# mazeSolver.net
KiCad netlist of a schematic drawn in EAGLE
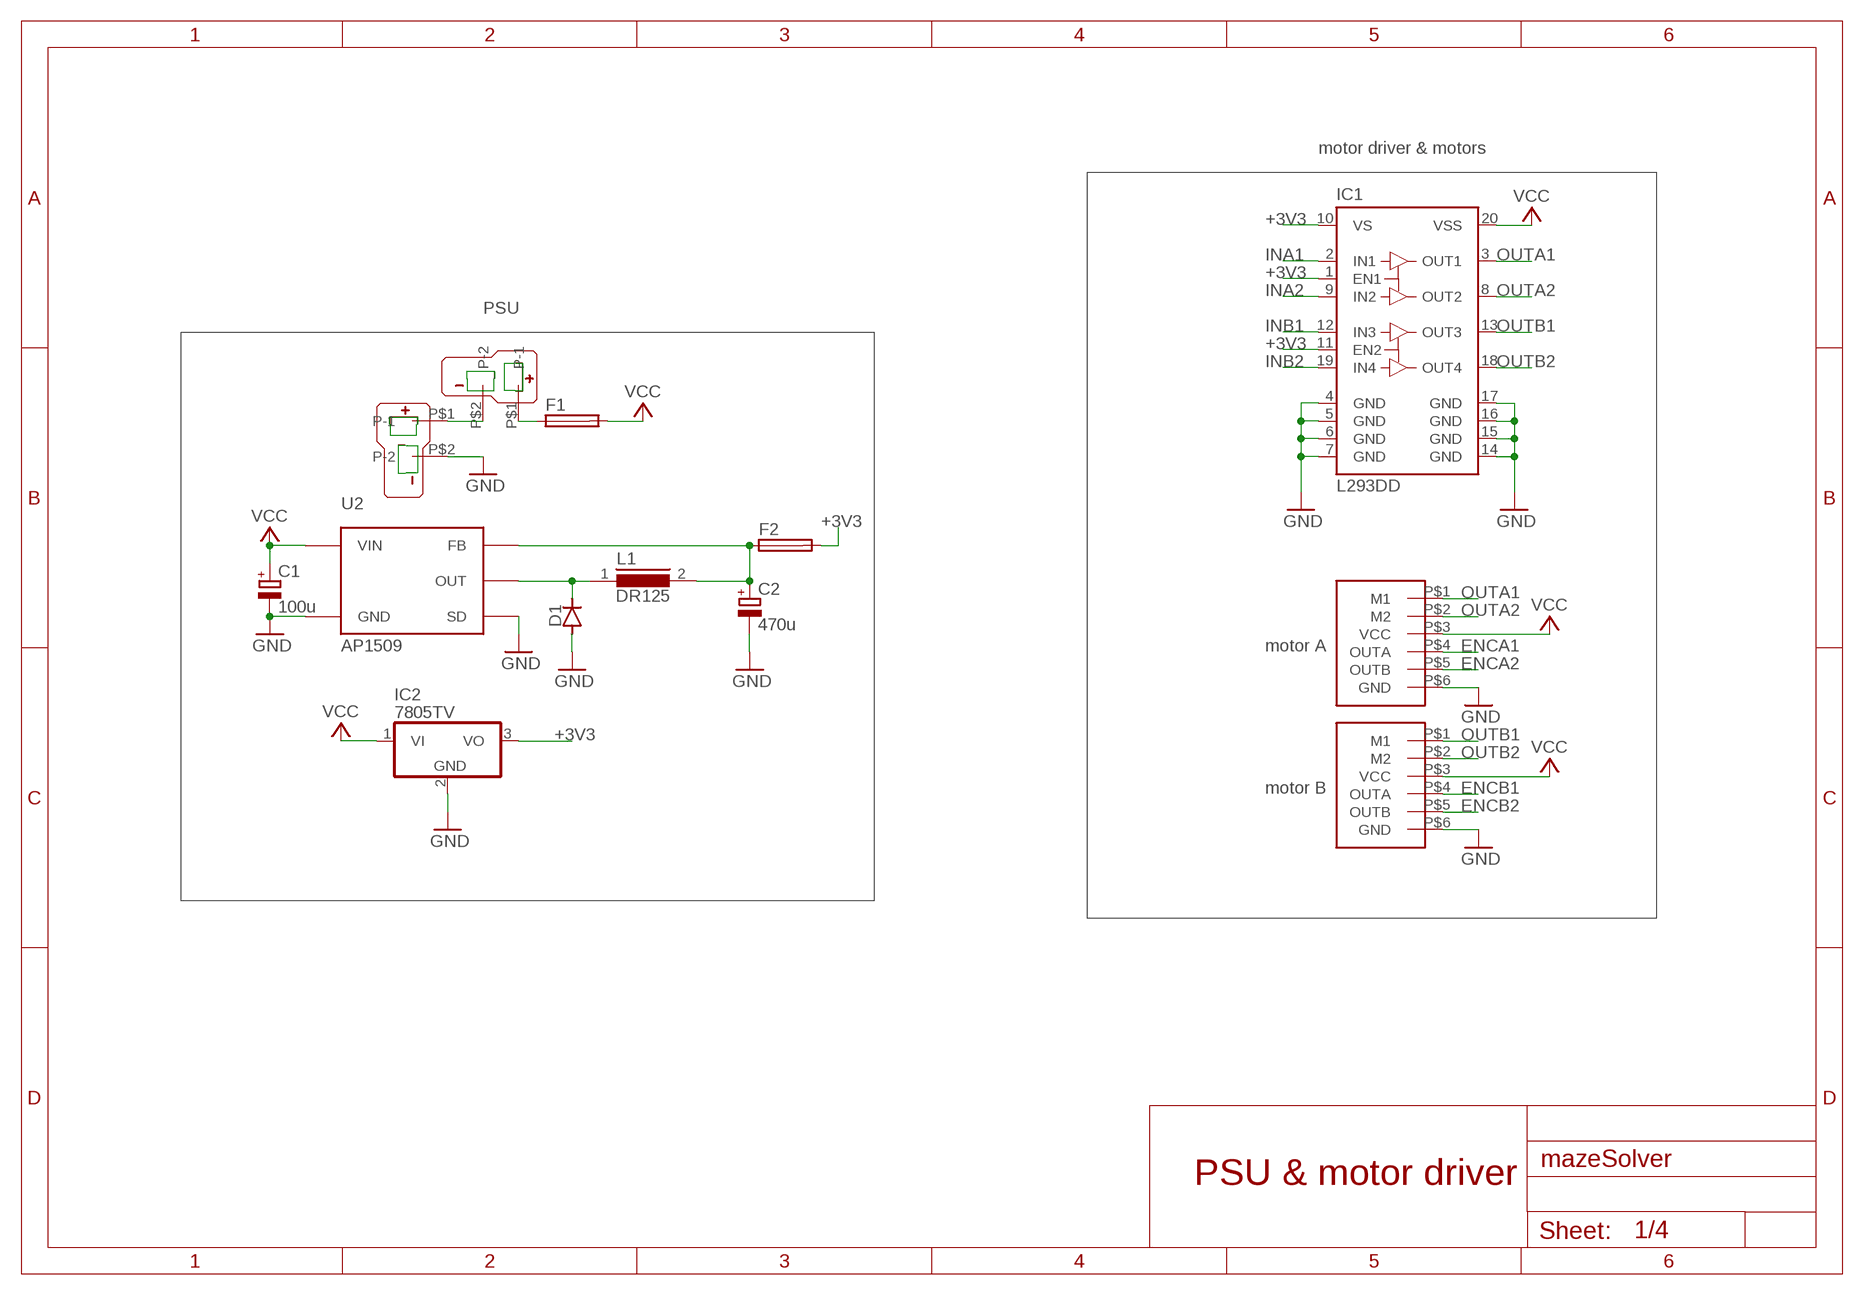
[diagram p0: schematic, sheet 1]
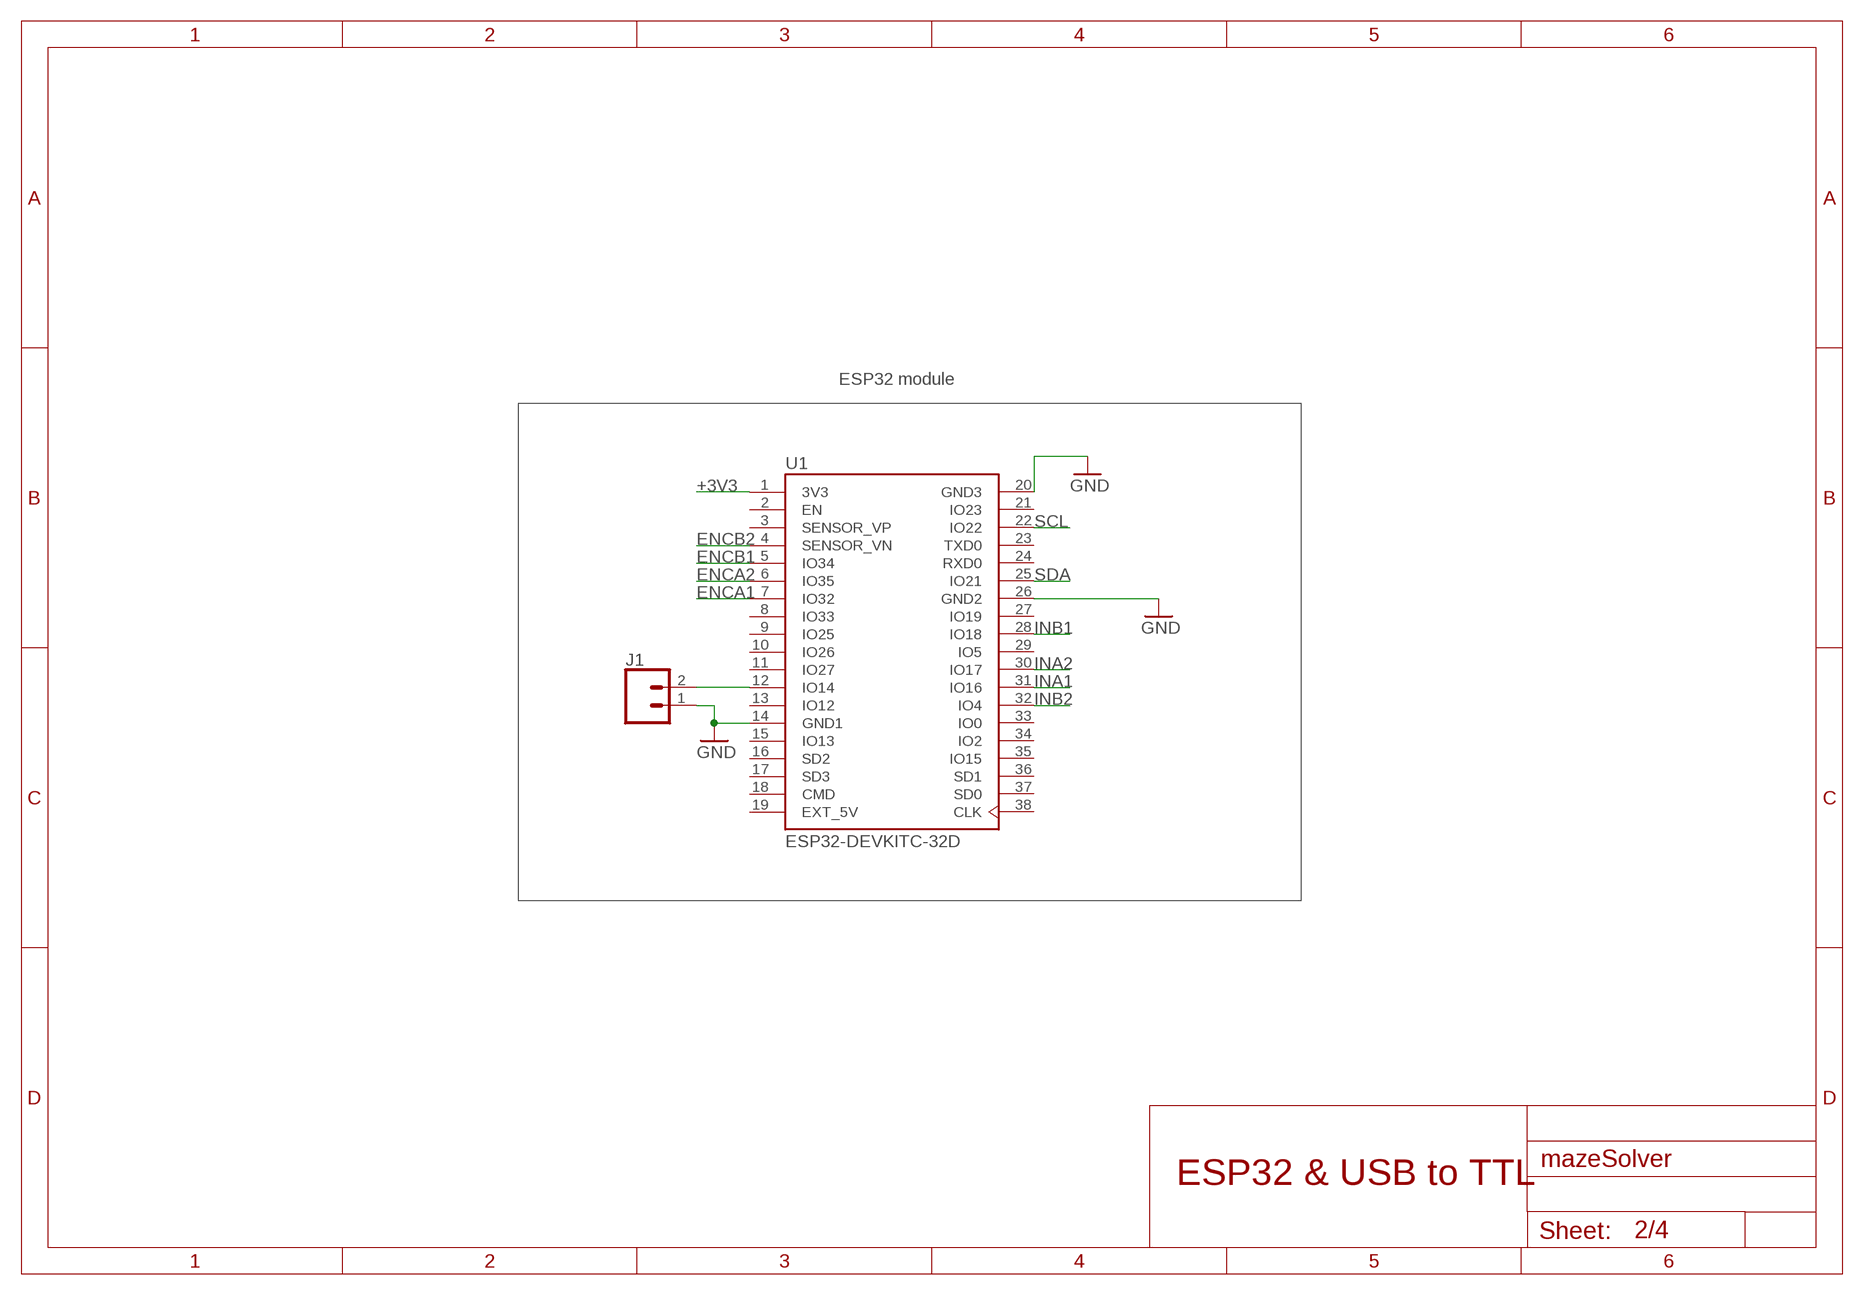
[diagram p1: schematic, sheet 2]
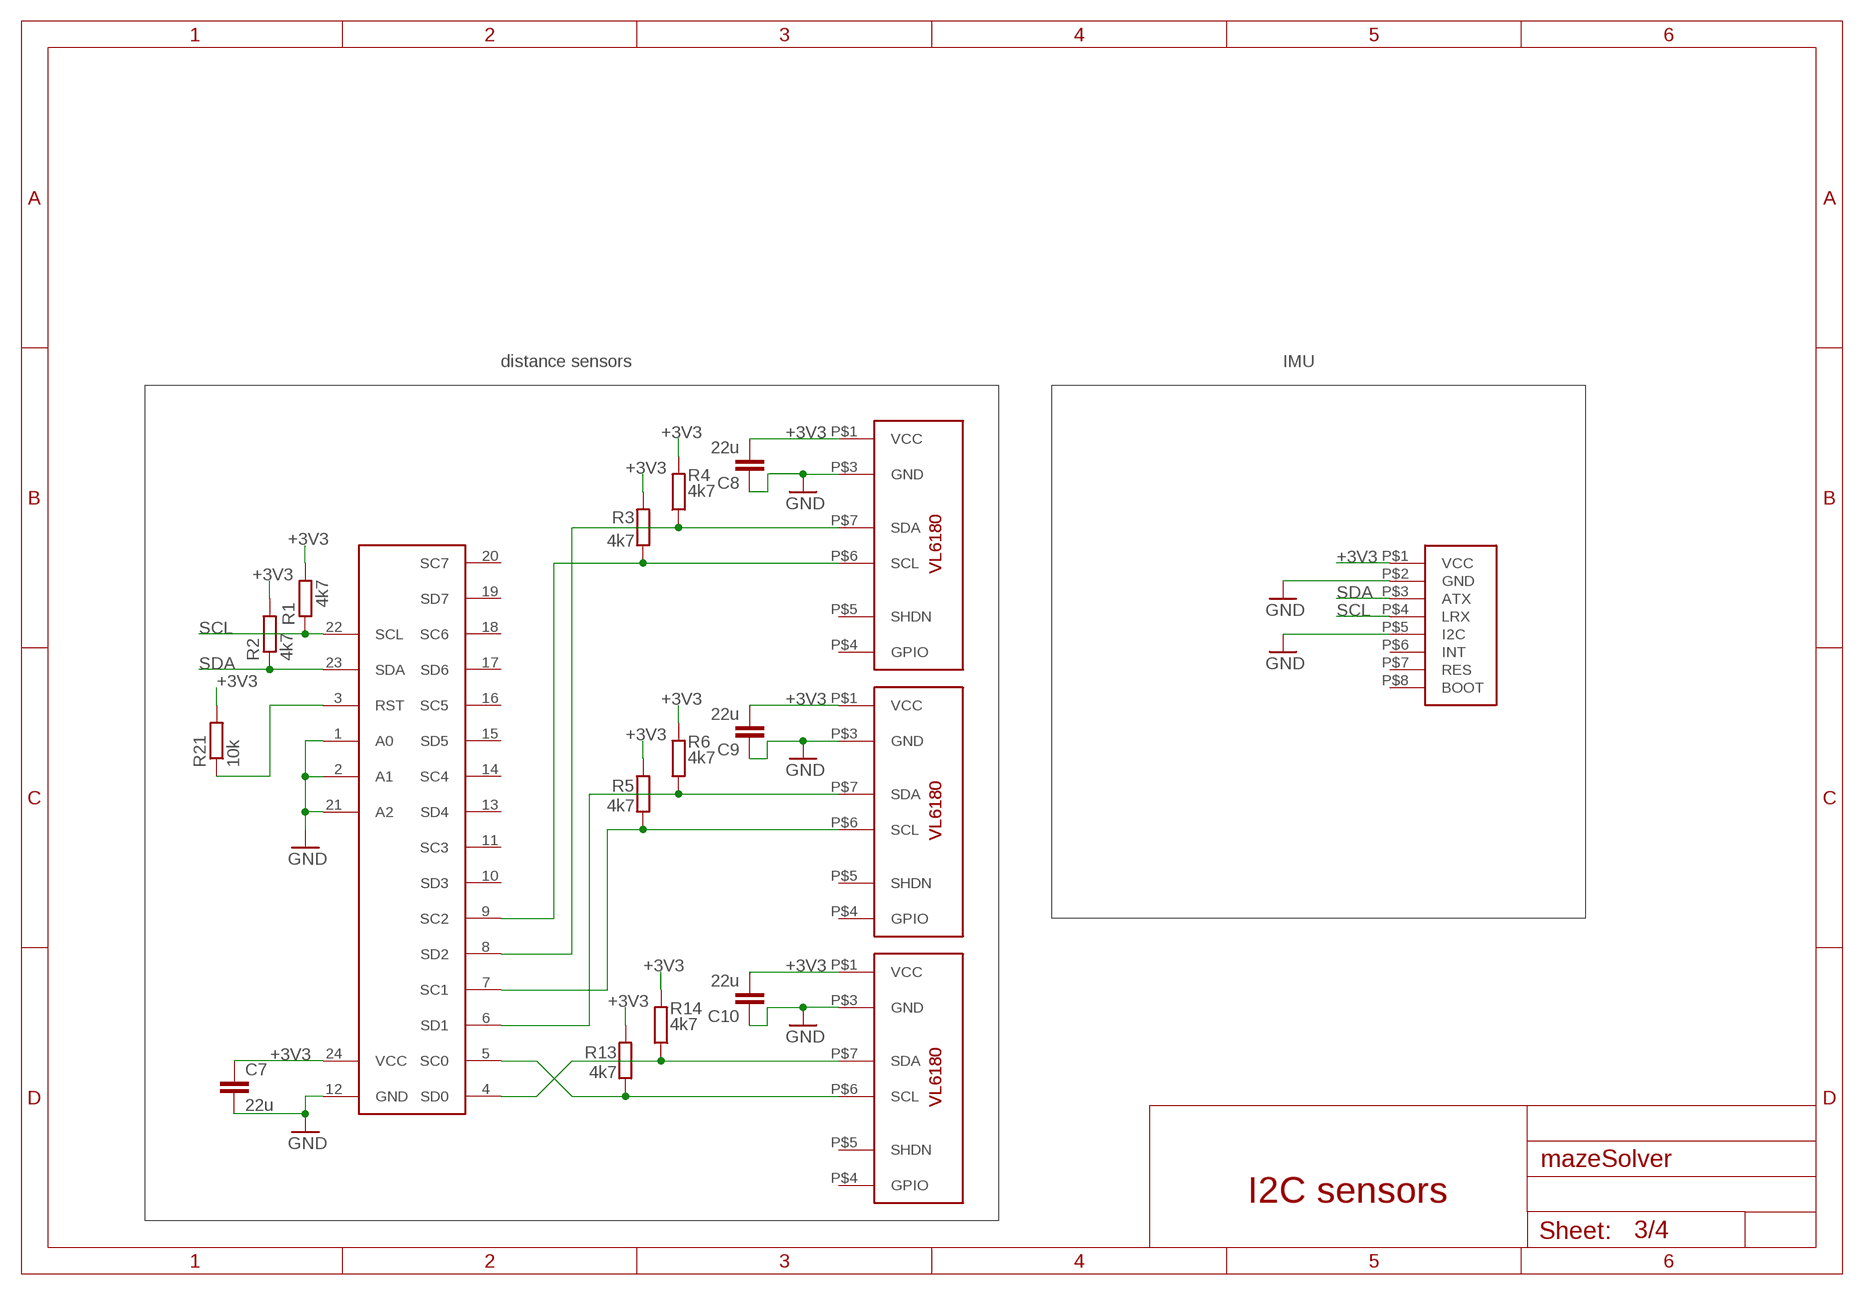
[diagram p2: schematic, sheet 3]

(export (version "E")
  (design (tool "Eeschema 10.0.6"))
  (components
    (comp (ref "J1")
      (value "CONN_02")
      (footprint "eagle-import:1X02")
      (libsource (lib "eagle-import") (part "CONN_02"))
    )
    (comp (ref "U1")
      (value "ESP32-DEVKITC-32D")
      (footprint "eagle-import:MODULE_ESP32-DEVKITC-32D")
      (fields (field (name "MF") "Espressif Systems"))
      (libsource (lib "eagle-import") (part "ESP32-DEVKITC-32D"))
    )
    (comp (ref "C1")
      (value "100u")
      (footprint "eagle-import:140CLH-0810")
      (fields (field (name "MF") "RUBYCON") (field (name "MPN") "100YXF100MEFC12.5X20"))
      (libsource (lib "eagle-import") (part "CPOL-EU140CLH-0810"))
    )
    (comp (ref "C2")
      (value "470u")
      (footprint "eagle-import:140CLH-0810")
      (libsource (lib "eagle-import") (part "CPOL-EU140CLH-0810"))
    )
    (comp (ref "D1")
      (value "DIODE-DO214AC")
      (footprint "eagle-import:DO214AC")
      (libsource (lib "eagle-import") (part "DIODE-DO214AC"))
    )
    (comp (ref "F1")
      (value "195591812")
      (footprint "eagle-import:C1812K")
      (libsource (lib "eagle-import") (part "195591812"))
    )
    (comp (ref "F2")
      (value "195591206")
      (footprint "eagle-import:C1206K")
      (libsource (lib "eagle-import") (part "195591206"))
    )
    (comp (ref "IC1")
      (value "L293DD")
      (footprint "eagle-import:SO20")
      (libsource (lib "eagle-import") (part "L293DD"))
    )
    (comp (ref "IC2")
      (value "7805TV")
      (footprint "eagle-import:TO220V")
      (libsource (lib "eagle-import") (part "78TV05"))
    )
    (comp (ref "L1")
      (value "DR125")
      (footprint "eagle-import:DR125")
      (libsource (lib "eagle-import") (part "DR125"))
    )
    (comp (ref "U$1")
      (value "T-PLUG_CONNECTOR")
      (footprint "eagle-import:T_PLUG_CONNECTOR")
      (libsource (lib "eagle-import") (part "T-PLUG_CONNECTOR"))
    )
    (comp (ref "U$2")
      (value "POLOLU_ENCODER")
      (footprint "eagle-import:POLOLU_ENCODER")
      (libsource (lib "eagle-import") (part "POLOLU_ENCODER"))
    )
    (comp (ref "U$3")
      (value "POLOLU_ENCODER")
      (footprint "eagle-import:POLOLU_ENCODER")
      (libsource (lib "eagle-import") (part "POLOLU_ENCODER"))
    )
    (comp (ref "U$9")
      (value "T-PLUG_CONNECTOR")
      (footprint "eagle-import:T_PLUG_CONNECTOR")
      (libsource (lib "eagle-import") (part "T-PLUG_CONNECTOR"))
    )
    (comp (ref "U2")
      (value "AP1509-SOP8L")
      (footprint "eagle-import:SOP-8L")
      (libsource (lib "eagle-import") (part "AP1509-SOP8L"))
    )
    (comp (ref "C7")
      (value "22u")
      (footprint "eagle-import:C1206")
      (libsource (lib "eagle-import") (part "C-EUC1206"))
    )
    (comp (ref "C8")
      (value "22u")
      (footprint "eagle-import:C1206")
      (libsource (lib "eagle-import") (part "C-EUC1206"))
    )
    (comp (ref "C9")
      (value "22u")
      (footprint "eagle-import:C1206")
      (libsource (lib "eagle-import") (part "C-EUC1206"))
    )
    (comp (ref "C10")
      (value "22u")
      (footprint "eagle-import:C1206")
      (libsource (lib "eagle-import") (part "C-EUC1206"))
    )
    (comp (ref "R1")
      (value "4k7")
      (footprint "eagle-import:R1206")
      (libsource (lib "eagle-import") (part "R-EU_R1206"))
    )
    (comp (ref "R2")
      (value "4k7")
      (footprint "eagle-import:R1206")
      (libsource (lib "eagle-import") (part "R-EU_R1206"))
    )
    (comp (ref "R3")
      (value "4k7")
      (footprint "eagle-import:R1206")
      (libsource (lib "eagle-import") (part "R-EU_R1206"))
    )
    (comp (ref "R4")
      (value "4k7")
      (footprint "eagle-import:R1206")
      (libsource (lib "eagle-import") (part "R-EU_R1206"))
    )
    (comp (ref "R5")
      (value "4k7")
      (footprint "eagle-import:R1206")
      (libsource (lib "eagle-import") (part "R-EU_R1206"))
    )
    (comp (ref "R6")
      (value "4k7")
      (footprint "eagle-import:R1206")
      (libsource (lib "eagle-import") (part "R-EU_R1206"))
    )
    (comp (ref "R13")
      (value "4k7")
      (footprint "eagle-import:R1206")
      (libsource (lib "eagle-import") (part "R-EU_R1206"))
    )
    (comp (ref "R14")
      (value "4k7")
      (footprint "eagle-import:R1206")
      (libsource (lib "eagle-import") (part "R-EU_R1206"))
    )
    (comp (ref "R21")
      (value "10k")
      (footprint "eagle-import:R1206")
      (libsource (lib "eagle-import") (part "R-EU_R1206"))
    )
    (comp (ref "U$4")
      (value "TDA9548")
      (footprint "eagle-import:SOIC24L")
      (libsource (lib "eagle-import") (part "TDA9548"))
    )
    (comp (ref "U$5")
      (value "VL6180X")
      (footprint "eagle-import:VL6180X")
      (libsource (lib "eagle-import") (part "VL6180X"))
    )
    (comp (ref "U$6")
      (value "VL6180X")
      (footprint "eagle-import:VL6180X")
      (libsource (lib "eagle-import") (part "VL6180X"))
    )
    (comp (ref "U$7")
      (value "VL6180X")
      (footprint "eagle-import:VL6180X")
      (libsource (lib "eagle-import") (part "VL6180X"))
    )
    (comp (ref "U$8")
      (value "BNO055")
      (footprint "eagle-import:BNO055")
      (libsource (lib "eagle-import") (part "BNO055"))
    )
  )
  (nets
    (net (code "1") (name "+3V3") (class "Default")
      (node (ref "C10") (pin "1") (pinfunction "1_1") (pintype "passive"))
      (node (ref "C7") (pin "1") (pinfunction "1_1") (pintype "passive"))
      (node (ref "C8") (pin "1") (pinfunction "1_1") (pintype "passive"))
      (node (ref "C9") (pin "1") (pinfunction "1_1") (pintype "passive"))
      (node (ref "F2") (pin "2") (pinfunction "2_2") (pintype "passive"))
      (node (ref "IC1") (pin "1") (pinfunction "EN1_1") (pintype "input"))
      (node (ref "IC1") (pin "10") (pinfunction "VS_10") (pintype "power_in"))
      (node (ref "IC1") (pin "11") (pinfunction "EN2_11") (pintype "input"))
      (node (ref "IC2") (pin "3") (pinfunction "VO_3") (pintype "passive"))
      (node (ref "R1") (pin "2") (pinfunction "2_2") (pintype "passive"))
      (node (ref "R13") (pin "2") (pinfunction "2_2") (pintype "passive"))
      (node (ref "R14") (pin "2") (pinfunction "2_2") (pintype "passive"))
      (node (ref "R2") (pin "2") (pinfunction "2_2") (pintype "passive"))
      (node (ref "R21") (pin "2") (pinfunction "2_2") (pintype "passive"))
      (node (ref "R3") (pin "2") (pinfunction "2_2") (pintype "passive"))
      (node (ref "R4") (pin "2") (pinfunction "2_2") (pintype "passive"))
      (node (ref "R5") (pin "2") (pinfunction "2_2") (pintype "passive"))
      (node (ref "R6") (pin "2") (pinfunction "2_2") (pintype "passive"))
      (node (ref "U$4") (pin "24") (pinfunction "VCC_24") (pintype "bidirectional"))
      (node (ref "U$5") (pin "P$1") (pinfunction "VCC_P$1") (pintype "bidirectional"))
      (node (ref "U$6") (pin "P$1") (pinfunction "VCC_P$1") (pintype "bidirectional"))
      (node (ref "U$7") (pin "P$1") (pinfunction "VCC_P$1") (pintype "bidirectional"))
      (node (ref "U$8") (pin "P$1") (pinfunction "VCC_P$1") (pintype "bidirectional"))
      (node (ref "U1") (pin "1") (pinfunction "3V3_1") (pintype "power_in"))
    )
    (net (code "2") (name "ENCA1") (class "Default")
      (node (ref "U$2") (pin "P$4") (pinfunction "OUTA_P$4") (pintype "bidirectional"))
      (node (ref "U1") (pin "7") (pinfunction "IO32_7") (pintype "bidirectional"))
    )
    (net (code "3") (name "ENCA2") (class "Default")
      (node (ref "U$2") (pin "P$5") (pinfunction "OUTB_P$5") (pintype "bidirectional"))
      (node (ref "U1") (pin "6") (pinfunction "IO35_6") (pintype "bidirectional"))
    )
    (net (code "4") (name "ENCB1") (class "Default")
      (node (ref "U$3") (pin "P$4") (pinfunction "OUTA_P$4") (pintype "bidirectional"))
      (node (ref "U1") (pin "5") (pinfunction "IO34_5") (pintype "bidirectional"))
    )
    (net (code "5") (name "ENCB2") (class "Default")
      (node (ref "U$3") (pin "P$5") (pinfunction "OUTB_P$5") (pintype "bidirectional"))
      (node (ref "U1") (pin "4") (pinfunction "SENSOR_VN_4") (pintype "input"))
    )
    (net (code "6") (name "EXT_5V") (class "Default")
      (node (ref "U1") (pin "19") (pinfunction "EXT_5V_19") (pintype "power_in"))
    )
    (net (code "7") (name "GND") (class "Default")
      (node (ref "C1") (pin "-") (pinfunction "-_-") (pintype "passive"))
      (node (ref "C10") (pin "2") (pinfunction "2_2") (pintype "passive"))
      (node (ref "C2") (pin "-") (pinfunction "-_-") (pintype "passive"))
      (node (ref "C7") (pin "2") (pinfunction "2_2") (pintype "passive"))
      (node (ref "C8") (pin "2") (pinfunction "2_2") (pintype "passive"))
      (node (ref "C9") (pin "2") (pinfunction "2_2") (pintype "passive"))
      (node (ref "D1") (pin "A") (pinfunction "A_A") (pintype "passive"))
      (node (ref "IC1") (pin "14") (pinfunction "GND_14") (pintype "power_in"))
      (node (ref "IC1") (pin "15") (pinfunction "GND_15") (pintype "power_in"))
      (node (ref "IC1") (pin "16") (pinfunction "GND_16") (pintype "power_in"))
      (node (ref "IC1") (pin "17") (pinfunction "GND_17") (pintype "power_in"))
      (node (ref "IC1") (pin "4") (pinfunction "GND_4") (pintype "power_in"))
      (node (ref "IC1") (pin "5") (pinfunction "GND_5") (pintype "power_in"))
      (node (ref "IC1") (pin "6") (pinfunction "GND_6") (pintype "power_in"))
      (node (ref "IC1") (pin "7") (pinfunction "GND_7") (pintype "power_in"))
      (node (ref "IC2") (pin "2") (pinfunction "GND_2") (pintype "passive"))
      (node (ref "J1") (pin "1") (pinfunction "1_1") (pintype "passive"))
      (node (ref "U$1") (pin "P$2") (pinfunction "P-2_P$2") (pintype "passive"))
      (node (ref "U$2") (pin "P$6") (pinfunction "GND_P$6") (pintype "bidirectional"))
      (node (ref "U$3") (pin "P$6") (pinfunction "GND_P$6") (pintype "bidirectional"))
      (node (ref "U$4") (pin "1") (pinfunction "A0_1") (pintype "bidirectional"))
      (node (ref "U$4") (pin "12") (pinfunction "GND_12") (pintype "bidirectional"))
      (node (ref "U$4") (pin "2") (pinfunction "A1_2") (pintype "bidirectional"))
      (node (ref "U$4") (pin "21") (pinfunction "A2_21") (pintype "bidirectional"))
      (node (ref "U$5") (pin "P$3") (pinfunction "GND_P$3") (pintype "bidirectional"))
      (node (ref "U$6") (pin "P$3") (pinfunction "GND_P$3") (pintype "bidirectional"))
      (node (ref "U$7") (pin "P$3") (pinfunction "GND_P$3") (pintype "bidirectional"))
      (node (ref "U$8") (pin "P$2") (pinfunction "GND_P$2") (pintype "bidirectional"))
      (node (ref "U$8") (pin "P$5") (pinfunction "I2C_P$5") (pintype "bidirectional"))
      (node (ref "U1") (pin "14") (pinfunction "GND1_14") (pintype "power_in"))
      (node (ref "U1") (pin "20") (pinfunction "GND3_20") (pintype "power_in"))
      (node (ref "U1") (pin "26") (pinfunction "GND2_26") (pintype "power_in"))
      (node (ref "U2") (pin "4") (pinfunction "SD_4") (pintype "bidirectional"))
      (node (ref "U2") (pin "5") (pinfunction "GND_5") (pintype "bidirectional"))
      (node (ref "U2") (pin "6") (pinfunction "GND_6") (pintype "bidirectional"))
      (node (ref "U2") (pin "7") (pinfunction "GND_7") (pintype "bidirectional"))
      (node (ref "U2") (pin "8") (pinfunction "GND_8") (pintype "bidirectional"))
    )
    (net (code "8") (name "INA1") (class "Default")
      (node (ref "IC1") (pin "2") (pinfunction "IN1_2") (pintype "input"))
      (node (ref "U1") (pin "31") (pinfunction "IO16_31") (pintype "bidirectional"))
    )
    (net (code "9") (name "INA2") (class "Default")
      (node (ref "IC1") (pin "9") (pinfunction "IN2_9") (pintype "input"))
      (node (ref "U1") (pin "30") (pinfunction "IO17_30") (pintype "bidirectional"))
    )
    (net (code "10") (name "INB1") (class "Default")
      (node (ref "IC1") (pin "12") (pinfunction "IN3_12") (pintype "input"))
      (node (ref "U1") (pin "28") (pinfunction "IO18_28") (pintype "bidirectional"))
    )
    (net (code "11") (name "INB2") (class "Default")
      (node (ref "IC1") (pin "19") (pinfunction "IN4_19") (pintype "input"))
      (node (ref "U1") (pin "32") (pinfunction "IO4_32") (pintype "bidirectional"))
    )
    (net (code "12") (name "Net-(U$1-P-1)") (class "Default")
      (node (ref "U$1") (pin "P$1") (pinfunction "P-1_P$1") (pintype "passive"))
      (node (ref "U$9") (pin "P$2") (pinfunction "P-2_P$2") (pintype "passive"))
    )
    (net (code "13") (name "Net-(U$4-RST)") (class "Default")
      (node (ref "R21") (pin "1") (pinfunction "1_1") (pintype "passive"))
      (node (ref "U$4") (pin "3") (pinfunction "RST_3") (pintype "bidirectional"))
    )
    (net (code "14") (name "Net-(U$4-SC0)") (class "Default")
      (node (ref "R13") (pin "1") (pinfunction "1_1") (pintype "passive"))
      (node (ref "U$4") (pin "5") (pinfunction "SC0_5") (pintype "bidirectional"))
      (node (ref "U$7") (pin "P$6") (pinfunction "SCL_P$6") (pintype "bidirectional"))
    )
    (net (code "15") (name "Net-(U$4-SC1)") (class "Default")
      (node (ref "R5") (pin "1") (pinfunction "1_1") (pintype "passive"))
      (node (ref "U$4") (pin "7") (pinfunction "SC1_7") (pintype "bidirectional"))
      (node (ref "U$6") (pin "P$6") (pinfunction "SCL_P$6") (pintype "bidirectional"))
    )
    (net (code "16") (name "Net-(U$4-SC2)") (class "Default")
      (node (ref "R3") (pin "1") (pinfunction "1_1") (pintype "passive"))
      (node (ref "U$4") (pin "9") (pinfunction "SC2_9") (pintype "bidirectional"))
      (node (ref "U$5") (pin "P$6") (pinfunction "SCL_P$6") (pintype "bidirectional"))
    )
    (net (code "17") (name "Net-(U$4-SD0)") (class "Default")
      (node (ref "R14") (pin "1") (pinfunction "1_1") (pintype "passive"))
      (node (ref "U$4") (pin "4") (pinfunction "SD0_4") (pintype "bidirectional"))
      (node (ref "U$7") (pin "P$7") (pinfunction "SDA_P$7") (pintype "bidirectional"))
    )
    (net (code "18") (name "Net-(U$4-SD1)") (class "Default")
      (node (ref "R6") (pin "1") (pinfunction "1_1") (pintype "passive"))
      (node (ref "U$4") (pin "6") (pinfunction "SD1_6") (pintype "bidirectional"))
      (node (ref "U$6") (pin "P$7") (pinfunction "SDA_P$7") (pintype "bidirectional"))
    )
    (net (code "19") (name "Net-(U$4-SD2)") (class "Default")
      (node (ref "R4") (pin "1") (pinfunction "1_1") (pintype "passive"))
      (node (ref "U$4") (pin "8") (pinfunction "SD2_8") (pintype "bidirectional"))
      (node (ref "U$5") (pin "P$7") (pinfunction "SDA_P$7") (pintype "bidirectional"))
    )
    (net (code "20") (name "Net-(U$9-P-1)") (class "Default")
      (node (ref "F1") (pin "1") (pinfunction "1_1") (pintype "passive"))
      (node (ref "U$9") (pin "P$1") (pinfunction "P-1_P$1") (pintype "passive"))
    )
    (net (code "21") (name "Net-(U1-IO14)") (class "Default")
      (node (ref "J1") (pin "2") (pinfunction "2_2") (pintype "passive"))
      (node (ref "U1") (pin "12") (pinfunction "IO14_12") (pintype "bidirectional"))
    )
    (net (code "22") (name "Net-(U2-FB)") (class "Default")
      (node (ref "C2") (pin "+") (pinfunction "+_+") (pintype "passive"))
      (node (ref "F2") (pin "1") (pinfunction "1_1") (pintype "passive"))
      (node (ref "L1") (pin "2") (pinfunction "2_2") (pintype "passive"))
      (node (ref "U2") (pin "3") (pinfunction "FB_3") (pintype "output"))
    )
    (net (code "23") (name "Net-(U2-OUT)") (class "Default")
      (node (ref "D1") (pin "C") (pinfunction "C_C") (pintype "passive"))
      (node (ref "L1") (pin "1") (pinfunction "1_1") (pintype "passive"))
      (node (ref "U2") (pin "2") (pinfunction "OUT_2") (pintype "power_in"))
    )
    (net (code "24") (name "OUTA1") (class "Default")
      (node (ref "IC1") (pin "3") (pinfunction "OUT1_3") (pintype "output"))
      (node (ref "U$2") (pin "P$1") (pinfunction "M1_P$1") (pintype "bidirectional"))
    )
    (net (code "25") (name "OUTA2") (class "Default")
      (node (ref "IC1") (pin "8") (pinfunction "OUT2_8") (pintype "output"))
      (node (ref "U$2") (pin "P$2") (pinfunction "M2_P$2") (pintype "bidirectional"))
    )
    (net (code "26") (name "OUTB1") (class "Default")
      (node (ref "IC1") (pin "13") (pinfunction "OUT3_13") (pintype "output"))
      (node (ref "U$3") (pin "P$1") (pinfunction "M1_P$1") (pintype "bidirectional"))
    )
    (net (code "27") (name "OUTB2") (class "Default")
      (node (ref "IC1") (pin "18") (pinfunction "OUT4_18") (pintype "output"))
      (node (ref "U$3") (pin "P$2") (pinfunction "M2_P$2") (pintype "bidirectional"))
    )
    (net (code "28") (name "SCL") (class "Default")
      (node (ref "R1") (pin "1") (pinfunction "1_1") (pintype "passive"))
      (node (ref "U$4") (pin "22") (pinfunction "SCL_22") (pintype "bidirectional"))
      (node (ref "U$8") (pin "P$4") (pinfunction "LRX_P$4") (pintype "bidirectional"))
      (node (ref "U1") (pin "22") (pinfunction "IO22_22") (pintype "bidirectional"))
    )
    (net (code "29") (name "SDA") (class "Default")
      (node (ref "R2") (pin "1") (pinfunction "1_1") (pintype "passive"))
      (node (ref "U$4") (pin "23") (pinfunction "SDA_23") (pintype "bidirectional"))
      (node (ref "U$8") (pin "P$3") (pinfunction "ATX_P$3") (pintype "bidirectional"))
      (node (ref "U1") (pin "25") (pinfunction "IO21_25") (pintype "bidirectional"))
    )
    (net (code "30") (name "VCC") (class "Default")
      (node (ref "C1") (pin "+") (pinfunction "+_+") (pintype "passive"))
      (node (ref "F1") (pin "2") (pinfunction "2_2") (pintype "passive"))
      (node (ref "IC1") (pin "20") (pinfunction "VSS_20") (pintype "power_in"))
      (node (ref "IC2") (pin "1") (pinfunction "VI_1") (pintype "input"))
      (node (ref "U$2") (pin "P$3") (pinfunction "VCC_P$3") (pintype "bidirectional"))
      (node (ref "U$3") (pin "P$3") (pinfunction "VCC_P$3") (pintype "bidirectional"))
      (node (ref "U2") (pin "1") (pinfunction "VIN_1") (pintype "power_in"))
    )
    (net (code "31") (name "unconnected-(U$4-SC3-Pad11)") (class "Default")
      (node (ref "U$4") (pin "11") (pinfunction "SC3_11") (pintype "bidirectional"))
    )
    (net (code "32") (name "unconnected-(U$4-SC4-Pad14)") (class "Default")
      (node (ref "U$4") (pin "14") (pinfunction "SC4_14") (pintype "bidirectional"))
    )
    (net (code "33") (name "unconnected-(U$4-SC5-Pad16)") (class "Default")
      (node (ref "U$4") (pin "16") (pinfunction "SC5_16") (pintype "bidirectional"))
    )
    (net (code "34") (name "unconnected-(U$4-SC6-Pad18)") (class "Default")
      (node (ref "U$4") (pin "18") (pinfunction "SC6_18") (pintype "bidirectional"))
    )
    (net (code "35") (name "unconnected-(U$4-SC7-Pad20)") (class "Default")
      (node (ref "U$4") (pin "20") (pinfunction "SC7_20") (pintype "bidirectional"))
    )
    (net (code "36") (name "unconnected-(U$4-SD3-Pad10)") (class "Default")
      (node (ref "U$4") (pin "10") (pinfunction "SD3_10") (pintype "bidirectional"))
    )
    (net (code "37") (name "unconnected-(U$4-SD4-Pad13)") (class "Default")
      (node (ref "U$4") (pin "13") (pinfunction "SD4_13") (pintype "bidirectional"))
    )
    (net (code "38") (name "unconnected-(U$4-SD5-Pad15)") (class "Default")
      (node (ref "U$4") (pin "15") (pinfunction "SD5_15") (pintype "bidirectional"))
    )
    (net (code "39") (name "unconnected-(U$4-SD6-Pad17)") (class "Default")
      (node (ref "U$4") (pin "17") (pinfunction "SD6_17") (pintype "bidirectional"))
    )
    (net (code "40") (name "unconnected-(U$4-SD7-Pad19)") (class "Default")
      (node (ref "U$4") (pin "19") (pinfunction "SD7_19") (pintype "bidirectional"))
    )
    (net (code "41") (name "unconnected-(U$5-GPIO-PadP$4)") (class "Default")
      (node (ref "U$5") (pin "P$4") (pinfunction "GPIO_P$4") (pintype "bidirectional"))
    )
    (net (code "42") (name "unconnected-(U$5-SHDN-PadP$5)") (class "Default")
      (node (ref "U$5") (pin "P$5") (pinfunction "SHDN_P$5") (pintype "bidirectional"))
    )
    (net (code "43") (name "unconnected-(U$6-GPIO-PadP$4)") (class "Default")
      (node (ref "U$6") (pin "P$4") (pinfunction "GPIO_P$4") (pintype "bidirectional"))
    )
    (net (code "44") (name "unconnected-(U$6-SHDN-PadP$5)") (class "Default")
      (node (ref "U$6") (pin "P$5") (pinfunction "SHDN_P$5") (pintype "bidirectional"))
    )
    (net (code "45") (name "unconnected-(U$7-GPIO-PadP$4)") (class "Default")
      (node (ref "U$7") (pin "P$4") (pinfunction "GPIO_P$4") (pintype "bidirectional"))
    )
    (net (code "46") (name "unconnected-(U$7-SHDN-PadP$5)") (class "Default")
      (node (ref "U$7") (pin "P$5") (pinfunction "SHDN_P$5") (pintype "bidirectional"))
    )
    (net (code "47") (name "unconnected-(U$8-BOOT-PadP$8)") (class "Default")
      (node (ref "U$8") (pin "P$8") (pinfunction "BOOT_P$8") (pintype "bidirectional"))
    )
    (net (code "48") (name "unconnected-(U$8-INT-PadP$6)") (class "Default")
      (node (ref "U$8") (pin "P$6") (pinfunction "INT_P$6") (pintype "bidirectional"))
    )
    (net (code "49") (name "unconnected-(U$8-RES-PadP$7)") (class "Default")
      (node (ref "U$8") (pin "P$7") (pinfunction "RES_P$7") (pintype "bidirectional"))
    )
    (net (code "50") (name "unconnected-(U1-CLK-Pad38)") (class "Default")
      (node (ref "U1") (pin "38") (pinfunction "CLK_38") (pintype "input"))
    )
    (net (code "51") (name "unconnected-(U1-CMD-Pad18)") (class "Default")
      (node (ref "U1") (pin "18") (pinfunction "CMD_18") (pintype "bidirectional"))
    )
    (net (code "52") (name "unconnected-(U1-EN-Pad2)") (class "Default")
      (node (ref "U1") (pin "2") (pinfunction "EN_2") (pintype "input"))
    )
    (net (code "53") (name "unconnected-(U1-IO0-Pad33)") (class "Default")
      (node (ref "U1") (pin "33") (pinfunction "IO0_33") (pintype "bidirectional"))
    )
    (net (code "54") (name "unconnected-(U1-IO2-Pad34)") (class "Default")
      (node (ref "U1") (pin "34") (pinfunction "IO2_34") (pintype "bidirectional"))
    )
    (net (code "55") (name "unconnected-(U1-IO5-Pad29)") (class "Default")
      (node (ref "U1") (pin "29") (pinfunction "IO5_29") (pintype "bidirectional"))
    )
    (net (code "56") (name "unconnected-(U1-IO12-Pad13)") (class "Default")
      (node (ref "U1") (pin "13") (pinfunction "IO12_13") (pintype "bidirectional"))
    )
    (net (code "57") (name "unconnected-(U1-IO13-Pad15)") (class "Default")
      (node (ref "U1") (pin "15") (pinfunction "IO13_15") (pintype "bidirectional"))
    )
    (net (code "58") (name "unconnected-(U1-IO15-Pad35)") (class "Default")
      (node (ref "U1") (pin "35") (pinfunction "IO15_35") (pintype "bidirectional"))
    )
    (net (code "59") (name "unconnected-(U1-IO19-Pad27)") (class "Default")
      (node (ref "U1") (pin "27") (pinfunction "IO19_27") (pintype "bidirectional"))
    )
    (net (code "60") (name "unconnected-(U1-IO23-Pad21)") (class "Default")
      (node (ref "U1") (pin "21") (pinfunction "IO23_21") (pintype "bidirectional"))
    )
    (net (code "61") (name "unconnected-(U1-IO25-Pad9)") (class "Default")
      (node (ref "U1") (pin "9") (pinfunction "IO25_9") (pintype "bidirectional"))
    )
    (net (code "62") (name "unconnected-(U1-IO26-Pad10)") (class "Default")
      (node (ref "U1") (pin "10") (pinfunction "IO26_10") (pintype "bidirectional"))
    )
    (net (code "63") (name "unconnected-(U1-IO27-Pad11)") (class "Default")
      (node (ref "U1") (pin "11") (pinfunction "IO27_11") (pintype "bidirectional"))
    )
    (net (code "64") (name "unconnected-(U1-IO33-Pad8)") (class "Default")
      (node (ref "U1") (pin "8") (pinfunction "IO33_8") (pintype "bidirectional"))
    )
    (net (code "65") (name "unconnected-(U1-RXD0-Pad24)") (class "Default")
      (node (ref "U1") (pin "24") (pinfunction "RXD0_24") (pintype "input"))
    )
    (net (code "66") (name "unconnected-(U1-SD0-Pad37)") (class "Default")
      (node (ref "U1") (pin "37") (pinfunction "SD0_37") (pintype "bidirectional"))
    )
    (net (code "67") (name "unconnected-(U1-SD1-Pad36)") (class "Default")
      (node (ref "U1") (pin "36") (pinfunction "SD1_36") (pintype "bidirectional"))
    )
    (net (code "68") (name "unconnected-(U1-SD2-Pad16)") (class "Default")
      (node (ref "U1") (pin "16") (pinfunction "SD2_16") (pintype "bidirectional"))
    )
    (net (code "69") (name "unconnected-(U1-SD3-Pad17)") (class "Default")
      (node (ref "U1") (pin "17") (pinfunction "SD3_17") (pintype "bidirectional"))
    )
    (net (code "70") (name "unconnected-(U1-SENSOR_VP-Pad3)") (class "Default")
      (node (ref "U1") (pin "3") (pinfunction "SENSOR_VP_3") (pintype "input"))
    )
    (net (code "71") (name "unconnected-(U1-TXD0-Pad23)") (class "Default")
      (node (ref "U1") (pin "23") (pinfunction "TXD0_23") (pintype "output"))
    )
  )
)
